# Sheet4.net
KiCad netlist of a schematic drawn in Altium Designer
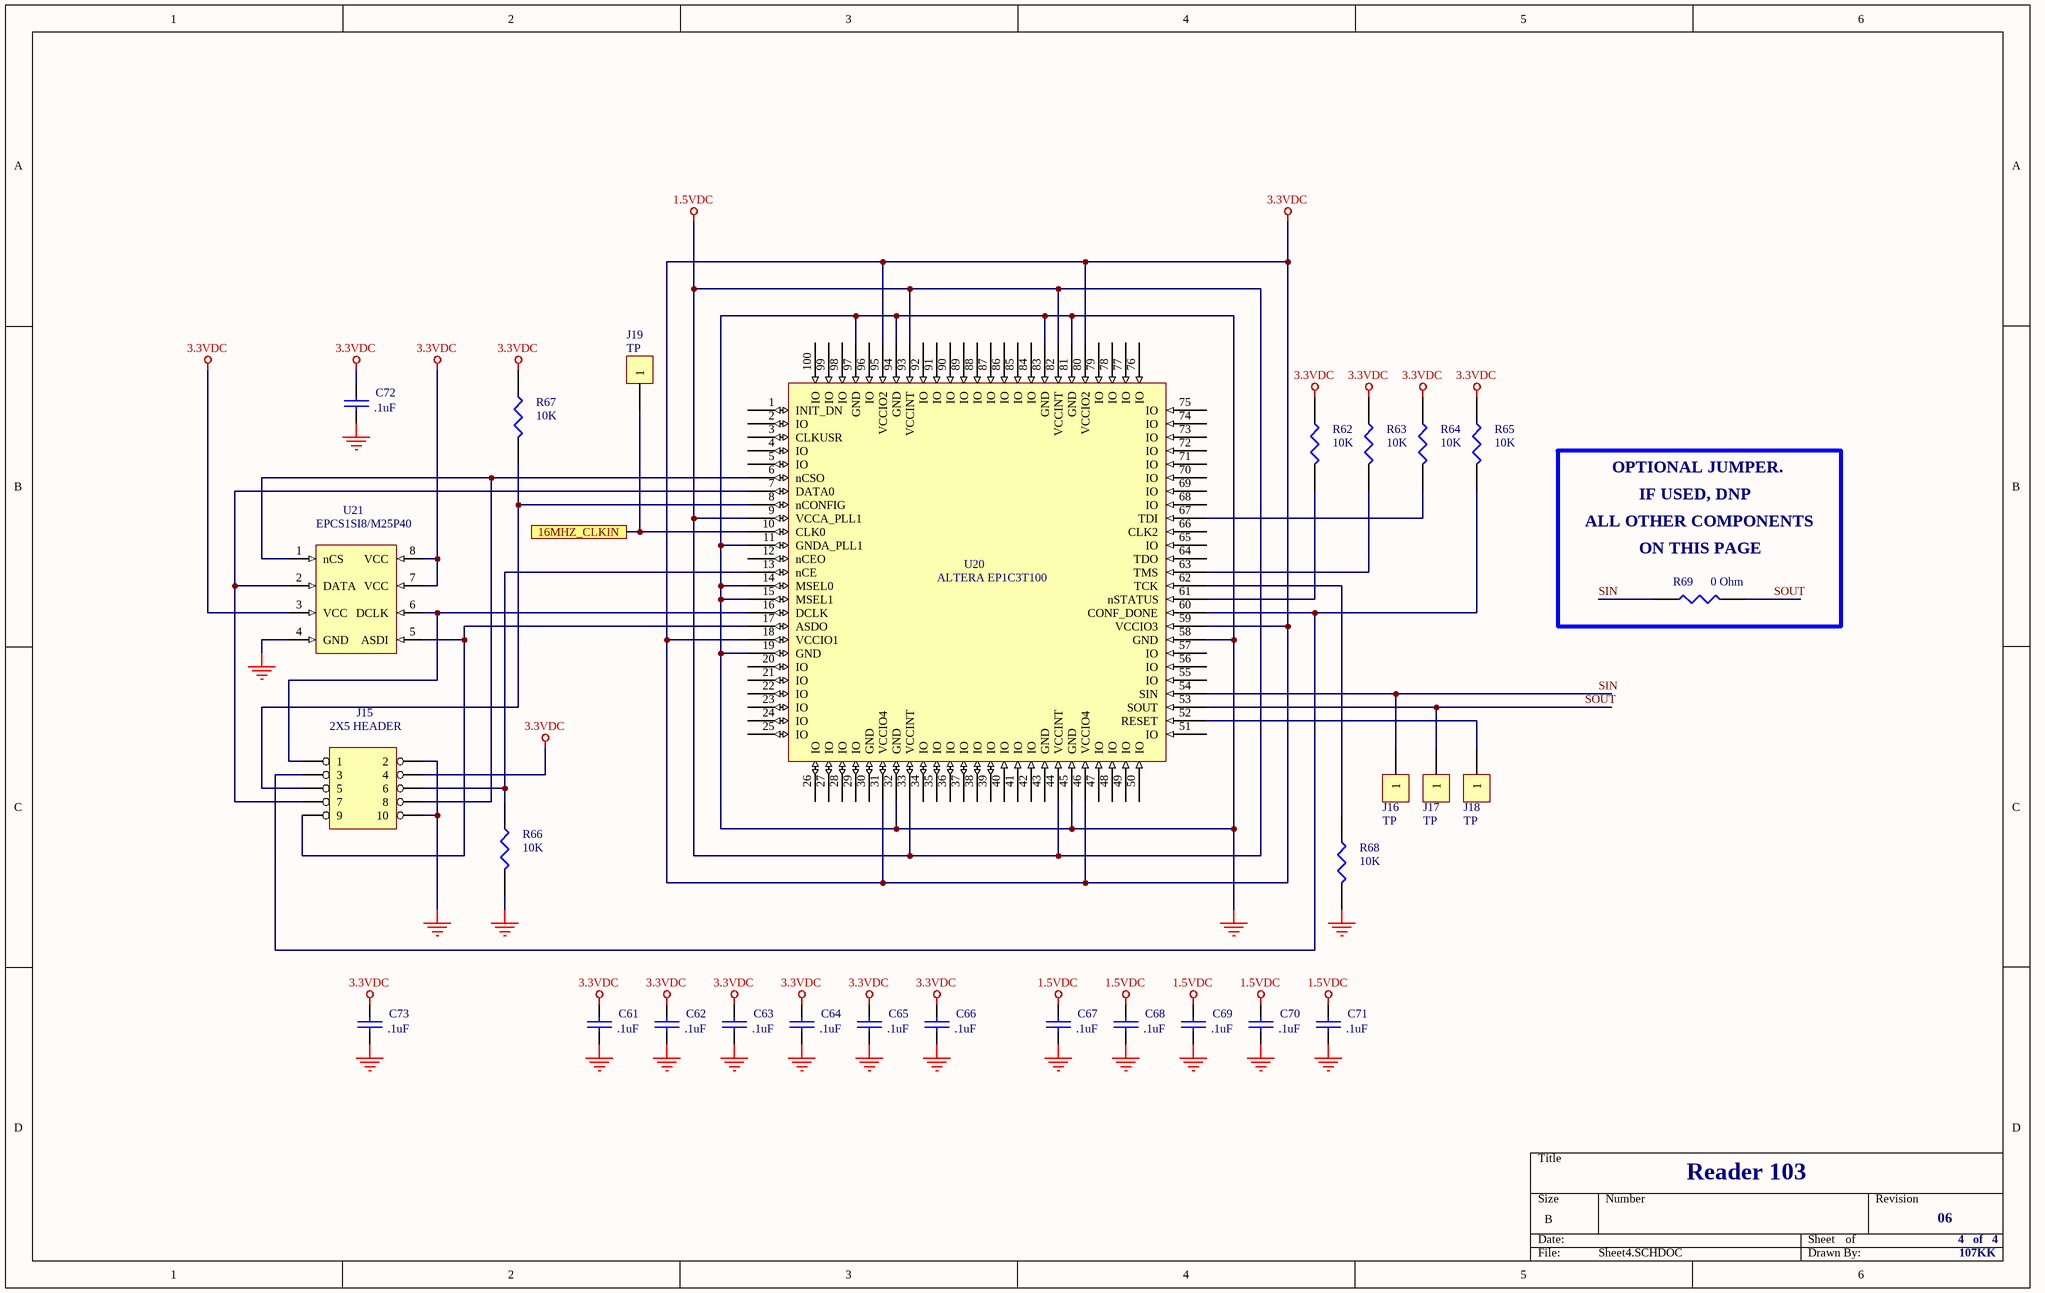
[diagram p0: Sheet4.SCHDOC]

(export (version "E")
  (design (tool "Eeschema 10.0.6"))
  (components
    (comp (ref "C61")
      (value ".1uF")
      (footprint "0603")
      (description "Capacitor")
      (libsource (lib "*") (part "CAP"))
    )
    (comp (ref "C62")
      (value ".1uF")
      (footprint "0603")
      (description "Capacitor")
      (libsource (lib "*") (part "CAP"))
    )
    (comp (ref "C63")
      (value ".1uF")
      (footprint "0603")
      (description "Capacitor")
      (libsource (lib "*") (part "CAP"))
    )
    (comp (ref "C64")
      (value ".1uF")
      (footprint "0603")
      (description "Capacitor")
      (libsource (lib "*") (part "CAP"))
    )
    (comp (ref "C65")
      (value ".1uF")
      (footprint "0603")
      (description "Capacitor")
      (libsource (lib "*") (part "CAP"))
    )
    (comp (ref "C66")
      (value ".1uF")
      (footprint "0603")
      (description "Capacitor")
      (libsource (lib "*") (part "CAP"))
    )
    (comp (ref "C67")
      (value ".1uF")
      (footprint "0603")
      (description "Capacitor")
      (libsource (lib "*") (part "CAP"))
    )
    (comp (ref "C68")
      (value ".1uF")
      (footprint "0603")
      (description "Capacitor")
      (libsource (lib "*") (part "CAP"))
    )
    (comp (ref "C69")
      (value ".1uF")
      (footprint "0603")
      (description "Capacitor")
      (libsource (lib "*") (part "CAP"))
    )
    (comp (ref "C70")
      (value ".1uF")
      (footprint "0603")
      (description "Capacitor")
      (libsource (lib "*") (part "CAP"))
    )
    (comp (ref "C71")
      (value ".1uF")
      (footprint "0603")
      (description "Capacitor")
      (libsource (lib "*") (part "CAP"))
    )
    (comp (ref "C72")
      (value ".1uF")
      (footprint "0603")
      (description "Capacitor")
      (libsource (lib "*") (part "CAP"))
    )
    (comp (ref "C73")
      (value ".1uF")
      (footprint "0603")
      (description "Capacitor")
      (libsource (lib "*") (part "CAP"))
    )
    (comp (ref "J15") (value "2X5 HEADER") (footprint "2X5 HEADER") (libsource (lib "*") (part "HEADER 5X2")))
    (comp (ref "J16")
      (value "TP")
      (footprint "TEST POINT PAD 3")
      (description "Connector")
      (libsource (lib "*") (part "CON1"))
    )
    (comp (ref "J17")
      (value "TP")
      (footprint "TEST POINT PAD 3")
      (description "Connector")
      (libsource (lib "*") (part "CON1"))
    )
    (comp (ref "J18")
      (value "TP")
      (footprint "TEST POINT PAD 3")
      (description "Connector")
      (libsource (lib "*") (part "CON1"))
    )
    (comp (ref "J19")
      (value "TP")
      (footprint "TEST POINT PAD 3")
      (description "Connector")
      (libsource (lib "") (part "CON1_1"))
    )
    (comp (ref "R62") (value "10K") (footprint "0603") (libsource (lib "*") (part "RES1")))
    (comp (ref "R63") (value "10K") (footprint "0603") (libsource (lib "*") (part "RES1")))
    (comp (ref "R64") (value "10K") (footprint "0603") (libsource (lib "*") (part "RES1")))
    (comp (ref "R65") (value "10K") (footprint "0603") (libsource (lib "*") (part "RES1")))
    (comp (ref "R66") (value "10K") (footprint "0603") (libsource (lib "*") (part "RES1")))
    (comp (ref "R67") (value "10K") (footprint "0603") (libsource (lib "*") (part "RES1")))
    (comp (ref "R68") (value "10K") (footprint "0603") (libsource (lib "*") (part "RES1")))
    (comp (ref "R69") (value "0 Ohm") (footprint "0603") (libsource (lib "*") (part "RES1")))
    (comp (ref "U20")
      (value "ALTERA EP1C3T100")
      (footprint "TQFP100")
      (libsource (lib "*") (part "ALTERA EP1C3T100"))
    )
    (comp (ref "U21")
      (value "EPCS1SI8/M25P40")
      (footprint "SO8")
      (libsource (lib "*") (part "EPCS1SI8/M25P40"))
    )
  )
  (nets
    (net (code "1") (name "/16MHZ_CLKIN") (class "Default")
      (node (ref "J19") (pin "1") (pinfunction "1_1") (pintype "passive"))
      (node (ref "U20") (pin "10") (pinfunction "CLK0_10") (pintype "bidirectional"))
    )
    (net (code "2") (name "/SIN") (class "Default")
      (node (ref "J16") (pin "1") (pinfunction "1_1") (pintype "passive"))
      (node (ref "R69") (pin "1") (pinfunction "1_1") (pintype "passive"))
      (node (ref "U20") (pin "54") (pinfunction "SIN_54") (pintype "input"))
    )
    (net (code "3") (name "/SOUT") (class "Default")
      (node (ref "J17") (pin "1") (pinfunction "1_1") (pintype "passive"))
      (node (ref "R69") (pin "2") (pinfunction "2_2") (pintype "passive"))
      (node (ref "U20") (pin "53") (pinfunction "SOUT_53") (pintype "input"))
    )
    (net (code "4") (name "1.5VDC") (class "Default")
      (node (ref "C67") (pin "1") (pinfunction "1_1") (pintype "passive"))
      (node (ref "C68") (pin "1") (pinfunction "1_1") (pintype "passive"))
      (node (ref "C69") (pin "1") (pinfunction "1_1") (pintype "passive"))
      (node (ref "C70") (pin "1") (pinfunction "1_1") (pintype "passive"))
      (node (ref "C71") (pin "1") (pinfunction "1_1") (pintype "passive"))
      (node (ref "U20") (pin "33") (pinfunction "VCCINT_33") (pintype "bidirectional"))
      (node (ref "U20") (pin "44") (pinfunction "VCCINT_44") (pintype "input"))
      (node (ref "U20") (pin "82") (pinfunction "VCCINT_82") (pintype "input"))
      (node (ref "U20") (pin "9") (pinfunction "VCCA_PLL1_9") (pintype "bidirectional"))
      (node (ref "U20") (pin "93") (pinfunction "VCCINT_93") (pintype "input"))
    )
    (net (code "5") (name "3.3VDC") (class "Default")
      (node (ref "C61") (pin "1") (pinfunction "1_1") (pintype "passive"))
      (node (ref "C62") (pin "1") (pinfunction "1_1") (pintype "passive"))
      (node (ref "C63") (pin "1") (pinfunction "1_1") (pintype "passive"))
      (node (ref "C64") (pin "1") (pinfunction "1_1") (pintype "passive"))
      (node (ref "C65") (pin "1") (pinfunction "1_1") (pintype "passive"))
      (node (ref "C66") (pin "1") (pinfunction "1_1") (pintype "passive"))
      (node (ref "C72") (pin "1") (pinfunction "1_1") (pintype "passive"))
      (node (ref "C73") (pin "1") (pinfunction "1_1") (pintype "passive"))
      (node (ref "J15") (pin "4") (pinfunction "4_4") (pintype "passive"))
      (node (ref "R62") (pin "1") (pinfunction "1_1") (pintype "passive"))
      (node (ref "R63") (pin "1") (pinfunction "1_1") (pintype "passive"))
      (node (ref "R64") (pin "1") (pinfunction "1_1") (pintype "passive"))
      (node (ref "R65") (pin "1") (pinfunction "1_1") (pintype "passive"))
      (node (ref "R67") (pin "1") (pinfunction "1_1") (pintype "passive"))
      (node (ref "U20") (pin "18") (pinfunction "VCCIO1_18") (pintype "bidirectional"))
      (node (ref "U20") (pin "31") (pinfunction "VCCIO4_31") (pintype "bidirectional"))
      (node (ref "U20") (pin "46") (pinfunction "VCCIO4_46") (pintype "input"))
      (node (ref "U20") (pin "59") (pinfunction "VCCIO3_59") (pintype "input"))
      (node (ref "U20") (pin "80") (pinfunction "VCCIO2_80") (pintype "input"))
      (node (ref "U20") (pin "95") (pinfunction "VCCIO2_95") (pintype "input"))
      (node (ref "U21") (pin "3") (pinfunction "VCC_3") (pintype "input"))
      (node (ref "U21") (pin "7") (pinfunction "VCC_7") (pintype "input"))
      (node (ref "U21") (pin "8") (pinfunction "VCC_8") (pintype "input"))
    )
    (net (code "6") (name "GND_COM") (class "Default")
      (node (ref "C61") (pin "2") (pinfunction "2_2") (pintype "passive"))
      (node (ref "C62") (pin "2") (pinfunction "2_2") (pintype "passive"))
      (node (ref "C63") (pin "2") (pinfunction "2_2") (pintype "passive"))
      (node (ref "C64") (pin "2") (pinfunction "2_2") (pintype "passive"))
      (node (ref "C65") (pin "2") (pinfunction "2_2") (pintype "passive"))
      (node (ref "C66") (pin "2") (pinfunction "2_2") (pintype "passive"))
      (node (ref "C67") (pin "2") (pinfunction "2_2") (pintype "passive"))
      (node (ref "C68") (pin "2") (pinfunction "2_2") (pintype "passive"))
      (node (ref "C69") (pin "2") (pinfunction "2_2") (pintype "passive"))
      (node (ref "C70") (pin "2") (pinfunction "2_2") (pintype "passive"))
      (node (ref "C71") (pin "2") (pinfunction "2_2") (pintype "passive"))
      (node (ref "C72") (pin "2") (pinfunction "2_2") (pintype "passive"))
      (node (ref "C73") (pin "2") (pinfunction "2_2") (pintype "passive"))
      (node (ref "J15") (pin "10") (pinfunction "10_10") (pintype "passive"))
      (node (ref "J15") (pin "2") (pinfunction "2_2") (pintype "passive"))
      (node (ref "R66") (pin "2") (pinfunction "2_2") (pintype "passive"))
      (node (ref "R68") (pin "2") (pinfunction "2_2") (pintype "passive"))
      (node (ref "U20") (pin "11") (pinfunction "GNDA_PLL1_11") (pintype "bidirectional"))
      (node (ref "U20") (pin "14") (pinfunction "MSEL0_14") (pintype "bidirectional"))
      (node (ref "U20") (pin "15") (pinfunction "MSEL1_15") (pintype "bidirectional"))
      (node (ref "U20") (pin "19") (pinfunction "GND_19") (pintype "bidirectional"))
      (node (ref "U20") (pin "32") (pinfunction "GND_32") (pintype "bidirectional"))
      (node (ref "U20") (pin "45") (pinfunction "GND_45") (pintype "input"))
      (node (ref "U20") (pin "58") (pinfunction "GND_58") (pintype "input"))
      (node (ref "U20") (pin "81") (pinfunction "GND_81") (pintype "input"))
      (node (ref "U20") (pin "83") (pinfunction "GND_83") (pintype "input"))
      (node (ref "U20") (pin "94") (pinfunction "GND_94") (pintype "input"))
      (node (ref "U20") (pin "97") (pinfunction "GND_97") (pintype "input"))
      (node (ref "U21") (pin "4") (pinfunction "GND_4") (pintype "input"))
    )
    (net (code "7") (name "Net-(U20-ASDO)") (class "Default")
      (node (ref "J15") (pin "9") (pinfunction "9_9") (pintype "passive"))
      (node (ref "U20") (pin "17") (pinfunction "ASDO_17") (pintype "bidirectional"))
      (node (ref "U21") (pin "5") (pinfunction "ASDI_5") (pintype "input"))
    )
    (net (code "8") (name "Net-(U20-CONF_DONE)") (class "Default")
      (node (ref "J15") (pin "3") (pinfunction "3_3") (pintype "passive"))
      (node (ref "R65") (pin "2") (pinfunction "2_2") (pintype "passive"))
      (node (ref "U20") (pin "60") (pinfunction "CONF_DONE_60") (pintype "input"))
    )
    (net (code "9") (name "Net-(U20-DATA0)") (class "Default")
      (node (ref "J15") (pin "7") (pinfunction "7_7") (pintype "passive"))
      (node (ref "U20") (pin "7") (pinfunction "DATA0_7") (pintype "bidirectional"))
      (node (ref "U21") (pin "2") (pinfunction "DATA_2") (pintype "input"))
    )
    (net (code "10") (name "Net-(U20-DCLK)") (class "Default")
      (node (ref "J15") (pin "1") (pinfunction "1_1") (pintype "passive"))
      (node (ref "U20") (pin "16") (pinfunction "DCLK_16") (pintype "bidirectional"))
      (node (ref "U21") (pin "6") (pinfunction "DCLK_6") (pintype "input"))
    )
    (net (code "11") (name "Net-(U20-RESET)") (class "Default")
      (node (ref "J18") (pin "1") (pinfunction "1_1") (pintype "passive"))
      (node (ref "U20") (pin "52") (pinfunction "RESET_52") (pintype "input"))
    )
    (net (code "12") (name "Net-(U20-TCK)") (class "Default")
      (node (ref "R68") (pin "1") (pinfunction "1_1") (pintype "passive"))
      (node (ref "U20") (pin "62") (pinfunction "TCK_62") (pintype "input"))
    )
    (net (code "13") (name "Net-(U20-TDI)") (class "Default")
      (node (ref "R64") (pin "2") (pinfunction "2_2") (pintype "passive"))
      (node (ref "U20") (pin "67") (pinfunction "TDI_67") (pintype "input"))
    )
    (net (code "14") (name "Net-(U20-TMS)") (class "Default")
      (node (ref "R63") (pin "2") (pinfunction "2_2") (pintype "passive"))
      (node (ref "U20") (pin "63") (pinfunction "TMS_63") (pintype "input"))
    )
    (net (code "15") (name "Net-(U20-nCE)") (class "Default")
      (node (ref "J15") (pin "6") (pinfunction "6_6") (pintype "passive"))
      (node (ref "R66") (pin "1") (pinfunction "1_1") (pintype "passive"))
      (node (ref "U20") (pin "13") (pinfunction "nCE_13") (pintype "bidirectional"))
    )
    (net (code "16") (name "Net-(U20-nCONFIG)") (class "Default")
      (node (ref "J15") (pin "5") (pinfunction "5_5") (pintype "passive"))
      (node (ref "R67") (pin "2") (pinfunction "2_2") (pintype "passive"))
      (node (ref "U20") (pin "8") (pinfunction "nCONFIG_8") (pintype "bidirectional"))
    )
    (net (code "17") (name "Net-(U20-nCSO)") (class "Default")
      (node (ref "J15") (pin "8") (pinfunction "8_8") (pintype "passive"))
      (node (ref "U20") (pin "6") (pinfunction "nCSO_6") (pintype "bidirectional"))
      (node (ref "U21") (pin "1") (pinfunction "nCS_1") (pintype "input"))
    )
    (net (code "18") (name "Net-(U20-nSTATUS)") (class "Default")
      (node (ref "R62") (pin "2") (pinfunction "2_2") (pintype "passive"))
      (node (ref "U20") (pin "61") (pinfunction "nSTATUS_61") (pintype "input"))
    )
    (net (code "19") (name "unconnected-(U20-CLK2-Pad66)") (class "Default")
      (node (ref "U20") (pin "66") (pinfunction "CLK2_66") (pintype "input"))
    )
    (net (code "20") (name "unconnected-(U20-CLKUSR-Pad3)") (class "Default")
      (node (ref "U20") (pin "3") (pinfunction "CLKUSR_3") (pintype "bidirectional"))
    )
    (net (code "21") (name "unconnected-(U20-GND-Pad30)") (class "Default")
      (node (ref "U20") (pin "30") (pinfunction "GND_30") (pintype "bidirectional"))
    )
    (net (code "22") (name "unconnected-(U20-GND-Pad43)") (class "Default")
      (node (ref "U20") (pin "43") (pinfunction "GND_43") (pintype "input"))
    )
    (net (code "23") (name "unconnected-(U20-INIT_DN-Pad1)") (class "Default")
      (node (ref "U20") (pin "1") (pinfunction "INIT_DN_1") (pintype "bidirectional"))
    )
    (net (code "24") (name "unconnected-(U20-IO-Pad2)") (class "Default")
      (node (ref "U20") (pin "2") (pinfunction "IO_2") (pintype "bidirectional"))
    )
    (net (code "25") (name "unconnected-(U20-IO-Pad4)") (class "Default")
      (node (ref "U20") (pin "4") (pinfunction "IO_4") (pintype "bidirectional"))
    )
    (net (code "26") (name "unconnected-(U20-IO-Pad5)") (class "Default")
      (node (ref "U20") (pin "5") (pinfunction "IO_5") (pintype "bidirectional"))
    )
    (net (code "27") (name "unconnected-(U20-IO-Pad20)") (class "Default")
      (node (ref "U20") (pin "20") (pinfunction "IO_20") (pintype "bidirectional"))
    )
    (net (code "28") (name "unconnected-(U20-IO-Pad21)") (class "Default")
      (node (ref "U20") (pin "21") (pinfunction "IO_21") (pintype "bidirectional"))
    )
    (net (code "29") (name "unconnected-(U20-IO-Pad22)") (class "Default")
      (node (ref "U20") (pin "22") (pinfunction "IO_22") (pintype "bidirectional"))
    )
    (net (code "30") (name "unconnected-(U20-IO-Pad23)") (class "Default")
      (node (ref "U20") (pin "23") (pinfunction "IO_23") (pintype "bidirectional"))
    )
    (net (code "31") (name "unconnected-(U20-IO-Pad24)") (class "Default")
      (node (ref "U20") (pin "24") (pinfunction "IO_24") (pintype "bidirectional"))
    )
    (net (code "32") (name "unconnected-(U20-IO-Pad25)") (class "Default")
      (node (ref "U20") (pin "25") (pinfunction "IO_25") (pintype "bidirectional"))
    )
    (net (code "33") (name "unconnected-(U20-IO-Pad26)") (class "Default")
      (node (ref "U20") (pin "26") (pinfunction "IO_26") (pintype "bidirectional"))
    )
    (net (code "34") (name "unconnected-(U20-IO-Pad27)") (class "Default")
      (node (ref "U20") (pin "27") (pinfunction "IO_27") (pintype "bidirectional"))
    )
    (net (code "35") (name "unconnected-(U20-IO-Pad28)") (class "Default")
      (node (ref "U20") (pin "28") (pinfunction "IO_28") (pintype "bidirectional"))
    )
    (net (code "36") (name "unconnected-(U20-IO-Pad29)") (class "Default")
      (node (ref "U20") (pin "29") (pinfunction "IO_29") (pintype "bidirectional"))
    )
    (net (code "37") (name "unconnected-(U20-IO-Pad34)") (class "Default")
      (node (ref "U20") (pin "34") (pinfunction "IO_34") (pintype "bidirectional"))
    )
    (net (code "38") (name "unconnected-(U20-IO-Pad35)") (class "Default")
      (node (ref "U20") (pin "35") (pinfunction "IO_35") (pintype "bidirectional"))
    )
    (net (code "39") (name "unconnected-(U20-IO-Pad36)") (class "Default")
      (node (ref "U20") (pin "36") (pinfunction "IO_36") (pintype "bidirectional"))
    )
    (net (code "40") (name "unconnected-(U20-IO-Pad37)") (class "Default")
      (node (ref "U20") (pin "37") (pinfunction "IO_37") (pintype "bidirectional"))
    )
    (net (code "41") (name "unconnected-(U20-IO-Pad38)") (class "Default")
      (node (ref "U20") (pin "38") (pinfunction "IO_38") (pintype "bidirectional"))
    )
    (net (code "42") (name "unconnected-(U20-IO-Pad39)") (class "Default")
      (node (ref "U20") (pin "39") (pinfunction "IO_39") (pintype "bidirectional"))
    )
    (net (code "43") (name "unconnected-(U20-IO-Pad40)") (class "Default")
      (node (ref "U20") (pin "40") (pinfunction "IO_40") (pintype "input"))
    )
    (net (code "44") (name "unconnected-(U20-IO-Pad41)") (class "Default")
      (node (ref "U20") (pin "41") (pinfunction "IO_41") (pintype "input"))
    )
    (net (code "45") (name "unconnected-(U20-IO-Pad42)") (class "Default")
      (node (ref "U20") (pin "42") (pinfunction "IO_42") (pintype "input"))
    )
    (net (code "46") (name "unconnected-(U20-IO-Pad47)") (class "Default")
      (node (ref "U20") (pin "47") (pinfunction "IO_47") (pintype "input"))
    )
    (net (code "47") (name "unconnected-(U20-IO-Pad48)") (class "Default")
      (node (ref "U20") (pin "48") (pinfunction "IO_48") (pintype "input"))
    )
    (net (code "48") (name "unconnected-(U20-IO-Pad49)") (class "Default")
      (node (ref "U20") (pin "49") (pinfunction "IO_49") (pintype "input"))
    )
    (net (code "49") (name "unconnected-(U20-IO-Pad50)") (class "Default")
      (node (ref "U20") (pin "50") (pinfunction "IO_50") (pintype "input"))
    )
    (net (code "50") (name "unconnected-(U20-IO-Pad51)") (class "Default")
      (node (ref "U20") (pin "51") (pinfunction "IO_51") (pintype "input"))
    )
    (net (code "51") (name "unconnected-(U20-IO-Pad55)") (class "Default")
      (node (ref "U20") (pin "55") (pinfunction "IO_55") (pintype "input"))
    )
    (net (code "52") (name "unconnected-(U20-IO-Pad56)") (class "Default")
      (node (ref "U20") (pin "56") (pinfunction "IO_56") (pintype "input"))
    )
    (net (code "53") (name "unconnected-(U20-IO-Pad57)") (class "Default")
      (node (ref "U20") (pin "57") (pinfunction "IO_57") (pintype "input"))
    )
    (net (code "54") (name "unconnected-(U20-IO-Pad65)") (class "Default")
      (node (ref "U20") (pin "65") (pinfunction "IO_65") (pintype "input"))
    )
    (net (code "55") (name "unconnected-(U20-IO-Pad68)") (class "Default")
      (node (ref "U20") (pin "68") (pinfunction "IO_68") (pintype "input"))
    )
    (net (code "56") (name "unconnected-(U20-IO-Pad69)") (class "Default")
      (node (ref "U20") (pin "69") (pinfunction "IO_69") (pintype "input"))
    )
    (net (code "57") (name "unconnected-(U20-IO-Pad70)") (class "Default")
      (node (ref "U20") (pin "70") (pinfunction "IO_70") (pintype "input"))
    )
    (net (code "58") (name "unconnected-(U20-IO-Pad71)") (class "Default")
      (node (ref "U20") (pin "71") (pinfunction "IO_71") (pintype "input"))
    )
    (net (code "59") (name "unconnected-(U20-IO-Pad72)") (class "Default")
      (node (ref "U20") (pin "72") (pinfunction "IO_72") (pintype "input"))
    )
    (net (code "60") (name "unconnected-(U20-IO-Pad73)") (class "Default")
      (node (ref "U20") (pin "73") (pinfunction "IO_73") (pintype "input"))
    )
    (net (code "61") (name "unconnected-(U20-IO-Pad74)") (class "Default")
      (node (ref "U20") (pin "74") (pinfunction "IO_74") (pintype "input"))
    )
    (net (code "62") (name "unconnected-(U20-IO-Pad75)") (class "Default")
      (node (ref "U20") (pin "75") (pinfunction "IO_75") (pintype "input"))
    )
    (net (code "63") (name "unconnected-(U20-IO-Pad76)") (class "Default")
      (node (ref "U20") (pin "76") (pinfunction "IO_76") (pintype "input"))
    )
    (net (code "64") (name "unconnected-(U20-IO-Pad77)") (class "Default")
      (node (ref "U20") (pin "77") (pinfunction "IO_77") (pintype "input"))
    )
    (net (code "65") (name "unconnected-(U20-IO-Pad78)") (class "Default")
      (node (ref "U20") (pin "78") (pinfunction "IO_78") (pintype "input"))
    )
    (net (code "66") (name "unconnected-(U20-IO-Pad79)") (class "Default")
      (node (ref "U20") (pin "79") (pinfunction "IO_79") (pintype "input"))
    )
    (net (code "67") (name "unconnected-(U20-IO-Pad84)") (class "Default")
      (node (ref "U20") (pin "84") (pinfunction "IO_84") (pintype "input"))
    )
    (net (code "68") (name "unconnected-(U20-IO-Pad85)") (class "Default")
      (node (ref "U20") (pin "85") (pinfunction "IO_85") (pintype "input"))
    )
    (net (code "69") (name "unconnected-(U20-IO-Pad86)") (class "Default")
      (node (ref "U20") (pin "86") (pinfunction "IO_86") (pintype "input"))
    )
    (net (code "70") (name "unconnected-(U20-IO-Pad87)") (class "Default")
      (node (ref "U20") (pin "87") (pinfunction "IO_87") (pintype "input"))
    )
    (net (code "71") (name "unconnected-(U20-IO-Pad88)") (class "Default")
      (node (ref "U20") (pin "88") (pinfunction "IO_88") (pintype "input"))
    )
    (net (code "72") (name "unconnected-(U20-IO-Pad89)") (class "Default")
      (node (ref "U20") (pin "89") (pinfunction "IO_89") (pintype "input"))
    )
    (net (code "73") (name "unconnected-(U20-IO-Pad90)") (class "Default")
      (node (ref "U20") (pin "90") (pinfunction "IO_90") (pintype "input"))
    )
    (net (code "74") (name "unconnected-(U20-IO-Pad91)") (class "Default")
      (node (ref "U20") (pin "91") (pinfunction "IO_91") (pintype "input"))
    )
    (net (code "75") (name "unconnected-(U20-IO-Pad92)") (class "Default")
      (node (ref "U20") (pin "92") (pinfunction "IO_92") (pintype "input"))
    )
    (net (code "76") (name "unconnected-(U20-IO-Pad96)") (class "Default")
      (node (ref "U20") (pin "96") (pinfunction "IO_96") (pintype "input"))
    )
    (net (code "77") (name "unconnected-(U20-IO-Pad98)") (class "Default")
      (node (ref "U20") (pin "98") (pinfunction "IO_98") (pintype "input"))
    )
    (net (code "78") (name "unconnected-(U20-IO-Pad99)") (class "Default")
      (node (ref "U20") (pin "99") (pinfunction "IO_99") (pintype "input"))
    )
    (net (code "79") (name "unconnected-(U20-IO-Pad100)") (class "Default")
      (node (ref "U20") (pin "100") (pinfunction "IO_100") (pintype "input"))
    )
    (net (code "80") (name "unconnected-(U20-TDO-Pad64)") (class "Default")
      (node (ref "U20") (pin "64") (pinfunction "TDO_64") (pintype "input"))
    )
    (net (code "81") (name "unconnected-(U20-nCEO-Pad12)") (class "Default")
      (node (ref "U20") (pin "12") (pinfunction "nCEO_12") (pintype "bidirectional"))
    )
  )
)
